# SparkFun_Qwiic_ToF_Imager_-_VL53L5CX_-_M.net
KiCad netlist of a schematic drawn in EAGLE
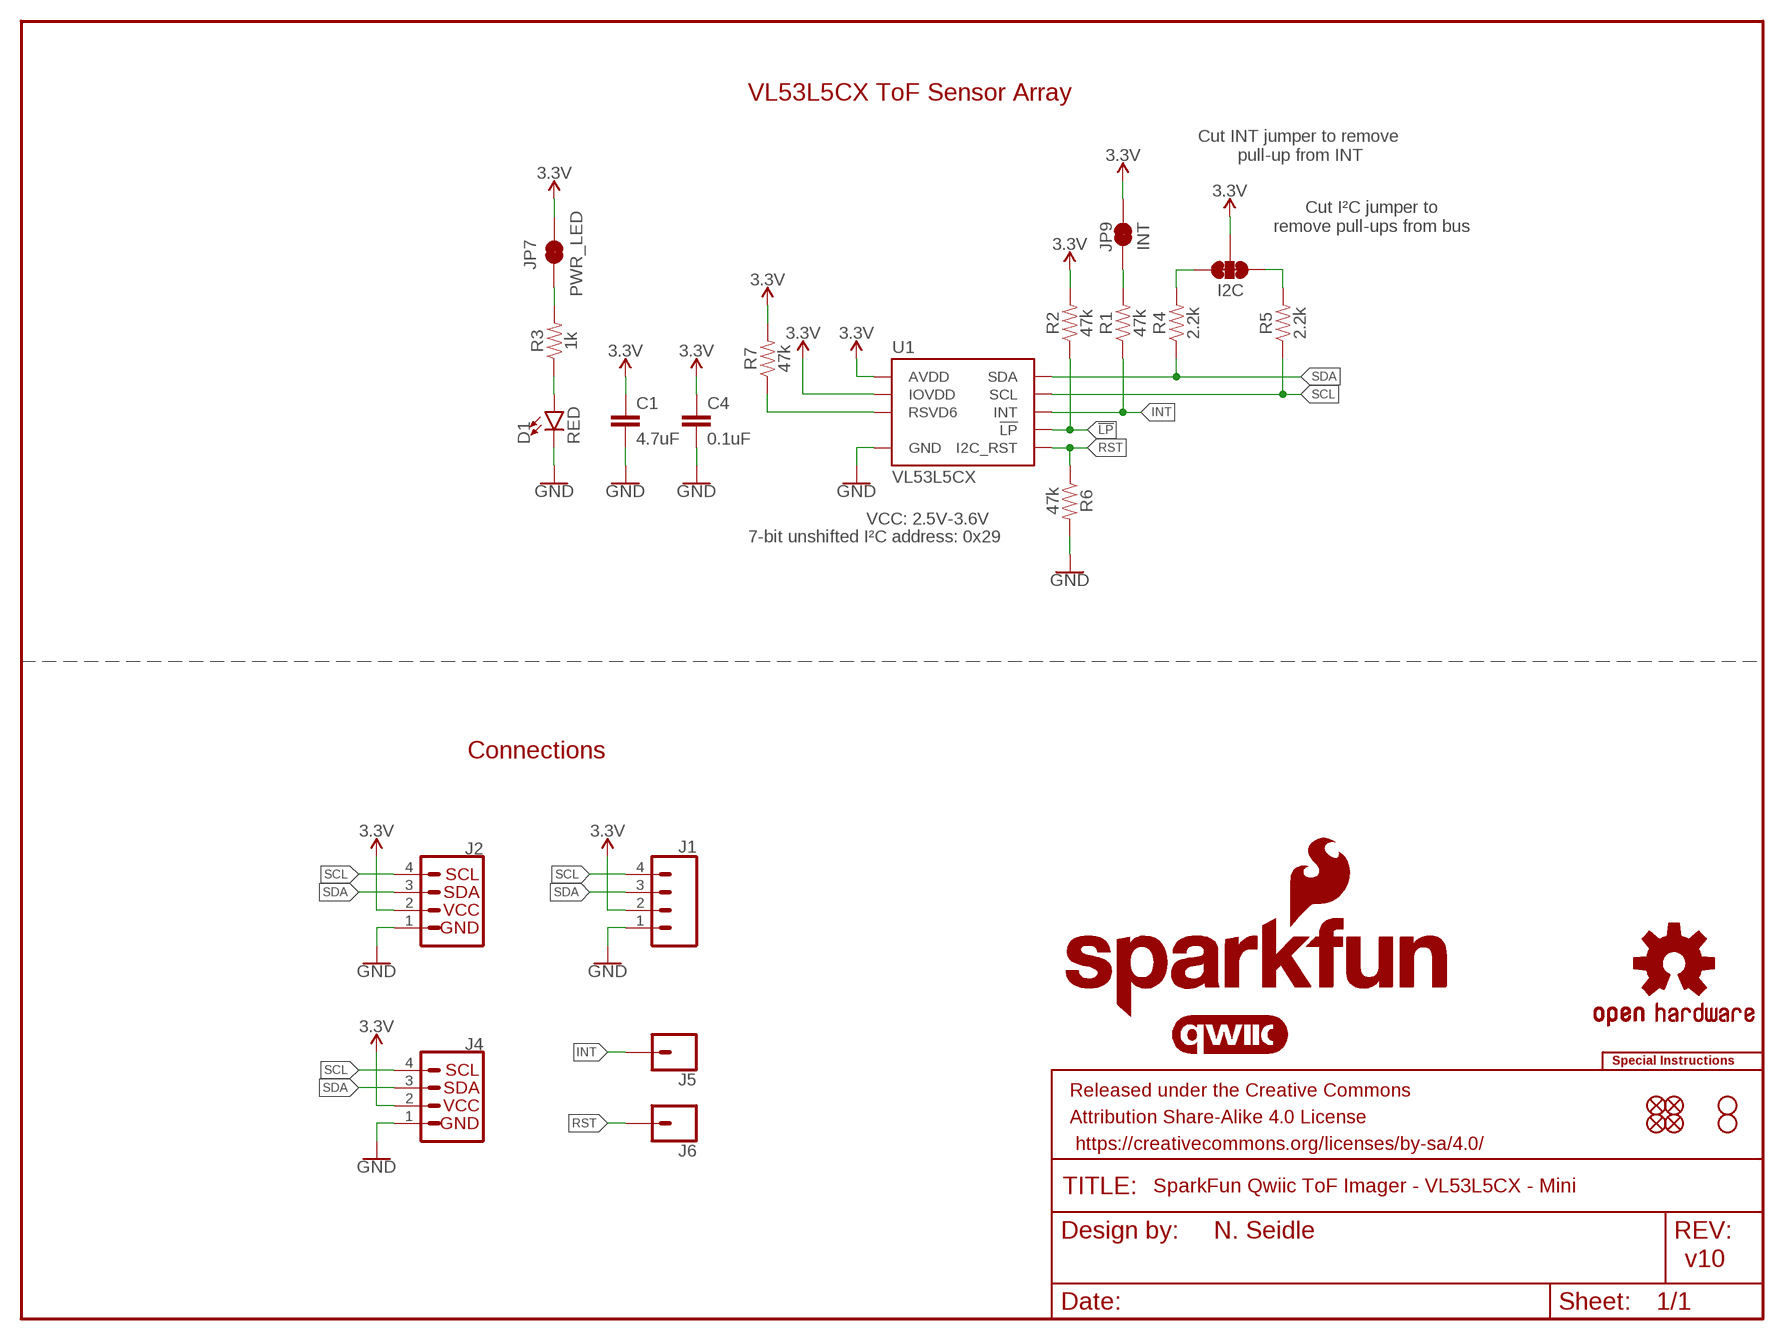
[diagram p0: schematic, sheet 1]

(export (version "E")
  (design (tool "Eeschema 10.0.6"))
  (components
    (comp (ref "C1")
      (value "4.7uF")
      (footprint "eagle-import:0402-TIGHT")
      (libsource (lib "eagle-import") (part "4.7UF-0402_TIGHT-6.3V-20%-X5R"))
    )
    (comp (ref "C4")
      (value "0.1uF")
      (footprint "eagle-import:0402-TIGHT")
      (libsource (lib "eagle-import") (part "0.1UF-0402T-6.3V-10%-X7R"))
    )
    (comp (ref "D1")
      (value "RED")
      (footprint "eagle-import:LED-0603")
      (libsource (lib "eagle-import") (part "LED-RED0603"))
    )
    (comp (ref "FRAME1")
      (value "FRAME-LETTER")
      (footprint "eagle-import:CREATIVE_COMMONS")
      (libsource (lib "eagle-import") (part "FRAME-LETTER"))
    )
    (comp (ref "I2C")
      (value "JUMPER-SMT_3_2-NC_TRACE_SILK")
      (footprint "eagle-import:SMT-JUMPER_3_2-NC_TRACE_SILK")
      (libsource (lib "eagle-import") (part "JUMPER-SMT_3_2-NC_TRACE_SILK"))
    )
    (comp (ref "J1")
      (value "CONN_041X04_NO_SILK")
      (footprint "eagle-import:1X04_NO_SILK")
      (libsource (lib "eagle-import") (part "CONN_041X04_NO_SILK"))
    )
    (comp (ref "J2")
      (value "Vertical Qwiic Connector")
      (footprint "eagle-import:JST04_1MM_VERT")
      (libsource (lib "eagle-import") (part "QWIIC_CONNECTOR"))
    )
    (comp (ref "J4")
      (value "Vertical Qwiic Connector")
      (footprint "eagle-import:JST04_1MM_VERT")
      (libsource (lib "eagle-import") (part "QWIIC_CONNECTOR"))
    )
    (comp (ref "J5")
      (value "CONN_01PTH_NO_SILK_YES_STOP")
      (footprint "eagle-import:1X01_NO_SILK")
      (libsource (lib "eagle-import") (part "CONN_01PTH_NO_SILK_YES_STOP"))
    )
    (comp (ref "J6")
      (value "CONN_01PTH_NO_SILK_YES_STOP")
      (footprint "eagle-import:1X01_NO_SILK")
      (libsource (lib "eagle-import") (part "CONN_01PTH_NO_SILK_YES_STOP"))
    )
    (comp (ref "JP1")
      (value "FIDUCIALUFIDUCIAL")
      (footprint "eagle-import:FIDUCIAL-MICRO")
      (libsource (lib "eagle-import") (part "FIDUCIALUFIDUCIAL"))
    )
    (comp (ref "JP2")
      (value "FIDUCIALUFIDUCIAL")
      (footprint "eagle-import:FIDUCIAL-MICRO")
      (libsource (lib "eagle-import") (part "FIDUCIALUFIDUCIAL"))
    )
    (comp (ref "JP5")
      (value "FIDUCIALUFIDUCIAL")
      (footprint "eagle-import:FIDUCIAL-MICRO")
      (libsource (lib "eagle-import") (part "FIDUCIALUFIDUCIAL"))
    )
    (comp (ref "JP6")
      (value "FIDUCIALUFIDUCIAL")
      (footprint "eagle-import:FIDUCIAL-MICRO")
      (libsource (lib "eagle-import") (part "FIDUCIALUFIDUCIAL"))
    )
    (comp (ref "JP7")
      (value "PWR_LED")
      (footprint "eagle-import:SMT-JUMPER_2_NC_TRACE_SILK")
      (libsource (lib "eagle-import") (part "JUMPER-SMT_2_NC_TRACE_SILK"))
    )
    (comp (ref "JP9")
      (value "INT")
      (footprint "eagle-import:SMT-JUMPER_2_NC_TRACE_SILK")
      (libsource (lib "eagle-import") (part "JUMPER-SMT_2_NC_TRACE_SILK"))
    )
    (comp (ref "JP10")
      (value "STAND-OFF")
      (footprint "eagle-import:STAND-OFF")
      (libsource (lib "eagle-import") (part "STAND-OFF"))
    )
    (comp (ref "JP11")
      (value "STAND-OFF")
      (footprint "eagle-import:STAND-OFF")
      (libsource (lib "eagle-import") (part "STAND-OFF"))
    )
    (comp (ref "LOGO1")
      (value "SFE_LOGO_NAME_FLAME8_MM")
      (footprint "eagle-import:SFE_LOGO_NAME_FLAME_8MM")
      (libsource (lib "eagle-import") (part "SFE_LOGO_NAME_FLAME8_MM"))
    )
    (comp (ref "LOGO2")
      (value "OSHW-LOGONO_SILK")
      (footprint "eagle-import:DUMMY")
      (libsource (lib "eagle-import") (part "OSHW-LOGONO_SILK"))
    )
    (comp (ref "LOGO3")
      (value "QWIIC_LOGO_CONNECTOR")
      (footprint "eagle-import:QWIIC_5.5MM")
      (libsource (lib "eagle-import") (part "QWIIC_LOGO_CONNECTOR"))
    )
    (comp (ref "LOGO4")
      (value "SFE_LOGO_NAME6_MM")
      (footprint "eagle-import:SFE_LOGO_NAME_6MM")
      (libsource (lib "eagle-import") (part "SFE_LOGO_NAME6_MM"))
    )
    (comp (ref "LOGO5")
      (value "SPECIAL_INSTRUCTIONS-ORDERING")
      (footprint "eagle-import:ORDERING_INSTRUCTIONS")
      (libsource (lib "eagle-import") (part "SPECIAL_INSTRUCTIONS-ORDERING"))
    )
    (comp (ref "R1")
      (value "47k")
      (footprint "eagle-import:0402-TIGHT")
      (libsource (lib "eagle-import") (part "47KOHM-0402-1/10W-1%"))
    )
    (comp (ref "R2")
      (value "47k")
      (footprint "eagle-import:0402-TIGHT")
      (libsource (lib "eagle-import") (part "47KOHM-0402-1/10W-1%"))
    )
    (comp (ref "R3")
      (value "1k")
      (footprint "eagle-import:0402-TIGHT")
      (libsource (lib "eagle-import") (part "1KOHM-0402T-1/16W-1%"))
    )
    (comp (ref "R4")
      (value "2.2k")
      (footprint "eagle-import:0402-TIGHT")
      (libsource (lib "eagle-import") (part "2.2KOHM-0402T-1/16W-1%"))
    )
    (comp (ref "R5")
      (value "2.2k")
      (footprint "eagle-import:0402-TIGHT")
      (libsource (lib "eagle-import") (part "2.2KOHM-0402T-1/16W-1%"))
    )
    (comp (ref "R6")
      (value "47k")
      (footprint "eagle-import:0402-TIGHT")
      (libsource (lib "eagle-import") (part "47KOHM-0402-1/10W-1%"))
    )
    (comp (ref "R7")
      (value "47k")
      (footprint "eagle-import:0402-TIGHT")
      (libsource (lib "eagle-import") (part "47KOHM-0402-1/10W-1%"))
    )
    (comp (ref "U1")
      (value "VL53L5CX")
      (footprint "eagle-import:VL53L5CX")
      (libsource (lib "eagle-import") (part "VL53L5CX"))
    )
  )
  (nets
    (net (code "1") (name "/~{LP}") (class "Default")
      (node (ref "R2") (pin "1") (pinfunction "1_1") (pintype "passive"))
      (node (ref "U1") (pin "A5") (pinfunction "~{LP}_A5") (pintype "bidirectional"))
    )
    (net (code "2") (name "3.3V") (class "Default")
      (node (ref "C1") (pin "1") (pinfunction "1_1") (pintype "passive"))
      (node (ref "C4") (pin "1") (pinfunction "1_1") (pintype "passive"))
      (node (ref "I2C") (pin "2") (pinfunction "2_2") (pintype "passive"))
      (node (ref "J1") (pin "2") (pinfunction "2_2") (pintype "passive"))
      (node (ref "J2") (pin "2") (pinfunction "2_2") (pintype "power_in"))
      (node (ref "J4") (pin "2") (pinfunction "2_2") (pintype "power_in"))
      (node (ref "JP7") (pin "2") (pinfunction "2_2") (pintype "passive"))
      (node (ref "JP9") (pin "2") (pinfunction "2_2") (pintype "passive"))
      (node (ref "R2") (pin "2") (pinfunction "2_2") (pintype "passive"))
      (node (ref "R7") (pin "2") (pinfunction "2_2") (pintype "passive"))
      (node (ref "U1") (pin "A4") (pinfunction "IOVDD_A4") (pintype "bidirectional"))
      (node (ref "U1") (pin "B1") (pinfunction "AVDD_B1") (pintype "bidirectional"))
      (node (ref "U1") (pin "B7") (pinfunction "AVDD_B7") (pintype "bidirectional"))
    )
    (net (code "3") (name "GND") (class "Default")
      (node (ref "C1") (pin "2") (pinfunction "2_2") (pintype "passive"))
      (node (ref "C4") (pin "2") (pinfunction "2_2") (pintype "passive"))
      (node (ref "D1") (pin "C") (pinfunction "C_C") (pintype "passive"))
      (node (ref "J1") (pin "1") (pinfunction "1_1") (pintype "passive"))
      (node (ref "J2") (pin "1") (pinfunction "1_1") (pintype "power_in"))
      (node (ref "J4") (pin "1") (pinfunction "1_1") (pintype "power_in"))
      (node (ref "R6") (pin "2") (pinfunction "2_2") (pintype "passive"))
      (node (ref "U1") (pin "A2") (pinfunction "GND_A2") (pintype "bidirectional"))
      (node (ref "U1") (pin "A6") (pinfunction "GND_A6") (pintype "bidirectional"))
      (node (ref "U1") (pin "A7") (pinfunction "GND_A7") (pintype "bidirectional"))
      (node (ref "U1") (pin "B4") (pinfunction "GND_B4") (pintype "bidirectional"))
      (node (ref "U1") (pin "C1") (pinfunction "GND_C1") (pintype "bidirectional"))
      (node (ref "U1") (pin "C6") (pinfunction "GND_C6") (pintype "bidirectional"))
      (node (ref "U1") (pin "C7") (pinfunction "GND_C7") (pintype "bidirectional"))
    )
    (net (code "4") (name "INT") (class "Default")
      (node (ref "J5") (pin "1") (pinfunction "1_1") (pintype "passive"))
      (node (ref "R1") (pin "1") (pinfunction "1_1") (pintype "passive"))
      (node (ref "U1") (pin "A3") (pinfunction "INT_A3") (pintype "bidirectional"))
    )
    (net (code "5") (name "Net-(D1-PadA)") (class "Default")
      (node (ref "D1") (pin "A") (pinfunction "A_A") (pintype "passive"))
      (node (ref "R3") (pin "1") (pinfunction "1_1") (pintype "passive"))
    )
    (net (code "6") (name "Net-(I2C-Pad1)") (class "Default")
      (node (ref "I2C") (pin "1") (pinfunction "1_1") (pintype "passive"))
      (node (ref "R5") (pin "2") (pinfunction "2_2") (pintype "passive"))
    )
    (net (code "7") (name "Net-(I2C-Pad3)") (class "Default")
      (node (ref "I2C") (pin "3") (pinfunction "3_3") (pintype "passive"))
      (node (ref "R4") (pin "2") (pinfunction "2_2") (pintype "passive"))
    )
    (net (code "8") (name "Net-(JP7-Pad1)") (class "Default")
      (node (ref "JP7") (pin "1") (pinfunction "1_1") (pintype "passive"))
      (node (ref "R3") (pin "2") (pinfunction "2_2") (pintype "passive"))
    )
    (net (code "9") (name "Net-(JP9-Pad1)") (class "Default")
      (node (ref "JP9") (pin "1") (pinfunction "1_1") (pintype "passive"))
      (node (ref "R1") (pin "2") (pinfunction "2_2") (pintype "passive"))
    )
    (net (code "10") (name "Net-(U1-RSVD6)") (class "Default")
      (node (ref "R7") (pin "1") (pinfunction "1_1") (pintype "passive"))
      (node (ref "U1") (pin "C2") (pinfunction "RSVD6_C2") (pintype "bidirectional"))
    )
    (net (code "11") (name "RST") (class "Default")
      (node (ref "J6") (pin "1") (pinfunction "1_1") (pintype "passive"))
      (node (ref "R6") (pin "1") (pinfunction "1_1") (pintype "passive"))
      (node (ref "U1") (pin "A1") (pinfunction "I2C_RST_A1") (pintype "bidirectional"))
    )
    (net (code "12") (name "SCL") (class "Default")
      (node (ref "J1") (pin "4") (pinfunction "4_4") (pintype "passive"))
      (node (ref "J2") (pin "4") (pinfunction "4_4") (pintype "passive"))
      (node (ref "J4") (pin "4") (pinfunction "4_4") (pintype "passive"))
      (node (ref "R5") (pin "1") (pinfunction "1_1") (pintype "passive"))
      (node (ref "U1") (pin "C4") (pinfunction "SCL_C4") (pintype "bidirectional"))
    )
    (net (code "13") (name "SDA") (class "Default")
      (node (ref "J1") (pin "3") (pinfunction "3_3") (pintype "passive"))
      (node (ref "J2") (pin "3") (pinfunction "3_3") (pintype "passive"))
      (node (ref "J4") (pin "3") (pinfunction "3_3") (pintype "passive"))
      (node (ref "R4") (pin "1") (pinfunction "1_1") (pintype "passive"))
      (node (ref "U1") (pin "C3") (pinfunction "SDA_C3") (pintype "bidirectional"))
    )
  )
)
